# gpi-filter.net
KiCad netlist of a schematic drawn in EAGLE
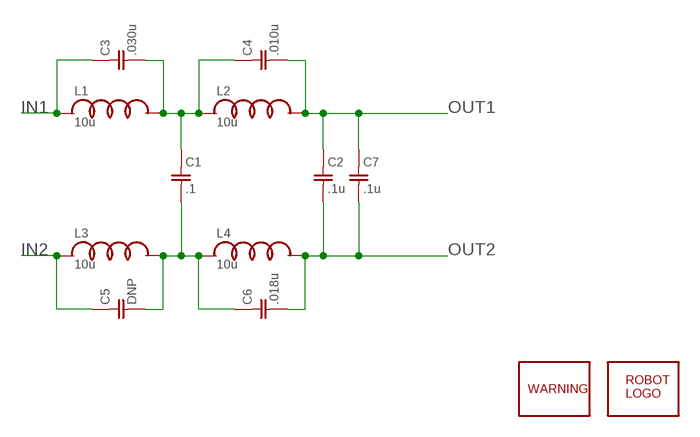
[diagram p0: schematic, sheet 1]

(export (version "E")
  (design (tool "Eeschema 10.0.6"))
  (components
    (comp (ref "C1")
      (value ".1")
      (footprint "eagle-import:SMD1210")
      (libsource (lib "eagle-import") (part "C1210"))
    )
    (comp (ref "C2")
      (value ".1u")
      (footprint "eagle-import:SMD1210")
      (libsource (lib "eagle-import") (part "C1210"))
    )
    (comp (ref "C3")
      (value ".030u")
      (footprint "eagle-import:SMD1210")
      (libsource (lib "eagle-import") (part "C1210"))
    )
    (comp (ref "C4")
      (value ".010u")
      (footprint "eagle-import:SMD1210")
      (libsource (lib "eagle-import") (part "C1210"))
    )
    (comp (ref "C5")
      (value "DNP")
      (footprint "eagle-import:SMD1210")
      (libsource (lib "eagle-import") (part "C1210"))
    )
    (comp (ref "C6")
      (value ".018u")
      (footprint "eagle-import:SMD1210")
      (libsource (lib "eagle-import") (part "C1210"))
    )
    (comp (ref "C7")
      (value ".1u")
      (footprint "eagle-import:SMD1210")
      (libsource (lib "eagle-import") (part "C1210"))
    )
    (comp (ref "L1")
      (value "10u")
      (footprint "eagle-import:XAL10")
      (libsource (lib "eagle-import") (part "LXAL10"))
    )
    (comp (ref "L2")
      (value "10u")
      (footprint "eagle-import:XAL10")
      (libsource (lib "eagle-import") (part "LXAL10"))
    )
    (comp (ref "L3")
      (value "10u")
      (footprint "eagle-import:XAL10")
      (libsource (lib "eagle-import") (part "LXAL10"))
    )
    (comp (ref "L4")
      (value "10u")
      (footprint "eagle-import:XAL10")
      (libsource (lib "eagle-import") (part "LXAL10"))
    )
    (comp (ref "U$1")
      (value "ROBOTMAN-LOGO")
      (footprint "eagle-import:ROBOTMAN-LOGO")
      (libsource (lib "eagle-import") (part "ROBOTMAN-LOGO"))
    )
    (comp (ref "U$2")
      (value "SYMBOL-WARNING")
      (footprint "eagle-import:SYMBOL-WARNING")
      (libsource (lib "eagle-import") (part "SYMBOL-WARNING"))
    )
  )
  (nets
    (net (code "1") (name "/IN1") (class "Default")
      (node (ref "C3") (pin "1") (pinfunction "P$1_1") (pintype "passive"))
      (node (ref "L1") (pin "P$1") (pinfunction "P$1_P$1") (pintype "passive"))
    )
    (net (code "2") (name "/IN2") (class "Default")
      (node (ref "C5") (pin "1") (pinfunction "P$1_1") (pintype "passive"))
      (node (ref "L3") (pin "P$1") (pinfunction "P$1_P$1") (pintype "passive"))
    )
    (net (code "3") (name "/OUT1") (class "Default")
      (node (ref "C2") (pin "1") (pinfunction "P$1_1") (pintype "passive"))
      (node (ref "C4") (pin "2") (pinfunction "P$2_2") (pintype "passive"))
      (node (ref "C7") (pin "1") (pinfunction "P$1_1") (pintype "passive"))
      (node (ref "L2") (pin "P$2") (pinfunction "P$2_P$2") (pintype "passive"))
    )
    (net (code "4") (name "/OUT2") (class "Default")
      (node (ref "C2") (pin "2") (pinfunction "P$2_2") (pintype "passive"))
      (node (ref "C6") (pin "2") (pinfunction "P$2_2") (pintype "passive"))
      (node (ref "C7") (pin "2") (pinfunction "P$2_2") (pintype "passive"))
      (node (ref "L4") (pin "P$2") (pinfunction "P$2_P$2") (pintype "passive"))
    )
    (net (code "5") (name "Net-(C1-P$1)") (class "Default")
      (node (ref "C1") (pin "1") (pinfunction "P$1_1") (pintype "passive"))
      (node (ref "C3") (pin "2") (pinfunction "P$2_2") (pintype "passive"))
      (node (ref "C4") (pin "1") (pinfunction "P$1_1") (pintype "passive"))
      (node (ref "L1") (pin "P$2") (pinfunction "P$2_P$2") (pintype "passive"))
      (node (ref "L2") (pin "P$1") (pinfunction "P$1_P$1") (pintype "passive"))
    )
    (net (code "6") (name "Net-(C1-P$2)") (class "Default")
      (node (ref "C1") (pin "2") (pinfunction "P$2_2") (pintype "passive"))
      (node (ref "C5") (pin "2") (pinfunction "P$2_2") (pintype "passive"))
      (node (ref "C6") (pin "1") (pinfunction "P$1_1") (pintype "passive"))
      (node (ref "L3") (pin "P$2") (pinfunction "P$2_P$2") (pintype "passive"))
      (node (ref "L4") (pin "P$1") (pinfunction "P$1_P$1") (pintype "passive"))
    )
  )
)
